# mma_breakout.net
KiCad netlist of a schematic drawn in EAGLE
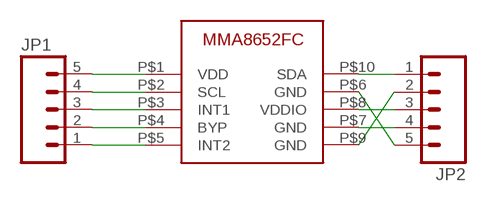
[diagram p0: schematic, sheet 1]

(export (version "E")
  (design (tool "Eeschema 10.0.6"))
  (components
    (comp (ref "JP1")
      (value "M05PTH")
      (footprint "eagle-import:1X05")
      (libsource (lib "eagle-import") (part "M05PTH"))
    )
    (comp (ref "JP2")
      (value "M05PTH")
      (footprint "eagle-import:1X05")
      (libsource (lib "eagle-import") (part "M05PTH"))
    )
    (comp (ref "U$1")
      (value "MMA8652FC")
      (footprint "eagle-import:MMA8652FC")
      (libsource (lib "eagle-import") (part "MMA8652FC"))
    )
  )
  (nets
    (net (code "1") (name "Net-(JP2-Pad2)") (class "Default")
      (node (ref "JP2") (pin "2") (pinfunction "2_2") (pintype "passive"))
      (node (ref "U$1") (pin "P$9") (pinfunction "GND_P$9") (pintype "power_in"))
    )
    (net (code "2") (name "Net-(JP2-Pad4)") (class "Default")
      (node (ref "JP2") (pin "4") (pinfunction "4_4") (pintype "passive"))
      (node (ref "U$1") (pin "P$7") (pinfunction "GND_P$7") (pintype "power_in"))
    )
    (net (code "3") (name "Net-(JP2-Pad5)") (class "Default")
      (node (ref "JP2") (pin "5") (pinfunction "5_5") (pintype "passive"))
      (node (ref "U$1") (pin "P$6") (pinfunction "GND_P$6") (pintype "power_in"))
    )
    (net (code "4") (name "Net-(U$1-BYP)") (class "Default")
      (node (ref "JP1") (pin "2") (pinfunction "2_2") (pintype "passive"))
      (node (ref "U$1") (pin "P$4") (pinfunction "BYP_P$4") (pintype "output"))
    )
    (net (code "5") (name "Net-(U$1-INT1)") (class "Default")
      (node (ref "JP1") (pin "3") (pinfunction "3_3") (pintype "passive"))
      (node (ref "U$1") (pin "P$3") (pinfunction "INT1_P$3") (pintype "output"))
    )
    (net (code "6") (name "Net-(U$1-INT2)") (class "Default")
      (node (ref "JP1") (pin "1") (pinfunction "1_1") (pintype "passive"))
      (node (ref "U$1") (pin "P$5") (pinfunction "INT2_P$5") (pintype "output"))
    )
    (net (code "7") (name "Net-(U$1-SCL)") (class "Default")
      (node (ref "JP1") (pin "4") (pinfunction "4_4") (pintype "passive"))
      (node (ref "U$1") (pin "P$2") (pinfunction "SCL_P$2") (pintype "bidirectional"))
    )
    (net (code "8") (name "Net-(U$1-SDA)") (class "Default")
      (node (ref "JP2") (pin "1") (pinfunction "1_1") (pintype "passive"))
      (node (ref "U$1") (pin "P$10") (pinfunction "SDA_P$10") (pintype "bidirectional"))
    )
    (net (code "9") (name "Net-(U$1-VDD)") (class "Default")
      (node (ref "JP1") (pin "5") (pinfunction "5_5") (pintype "passive"))
      (node (ref "U$1") (pin "P$1") (pinfunction "VDD_P$1") (pintype "power_in"))
    )
    (net (code "10") (name "Net-(U$1-VDDIO)") (class "Default")
      (node (ref "JP2") (pin "3") (pinfunction "3_3") (pintype "passive"))
      (node (ref "U$1") (pin "P$8") (pinfunction "VDDIO_P$8") (pintype "power_in"))
    )
  )
)
